# 4_waffling60-ALPS_periferals.net
KiCad netlist of a schematic drawn in Altium Designer
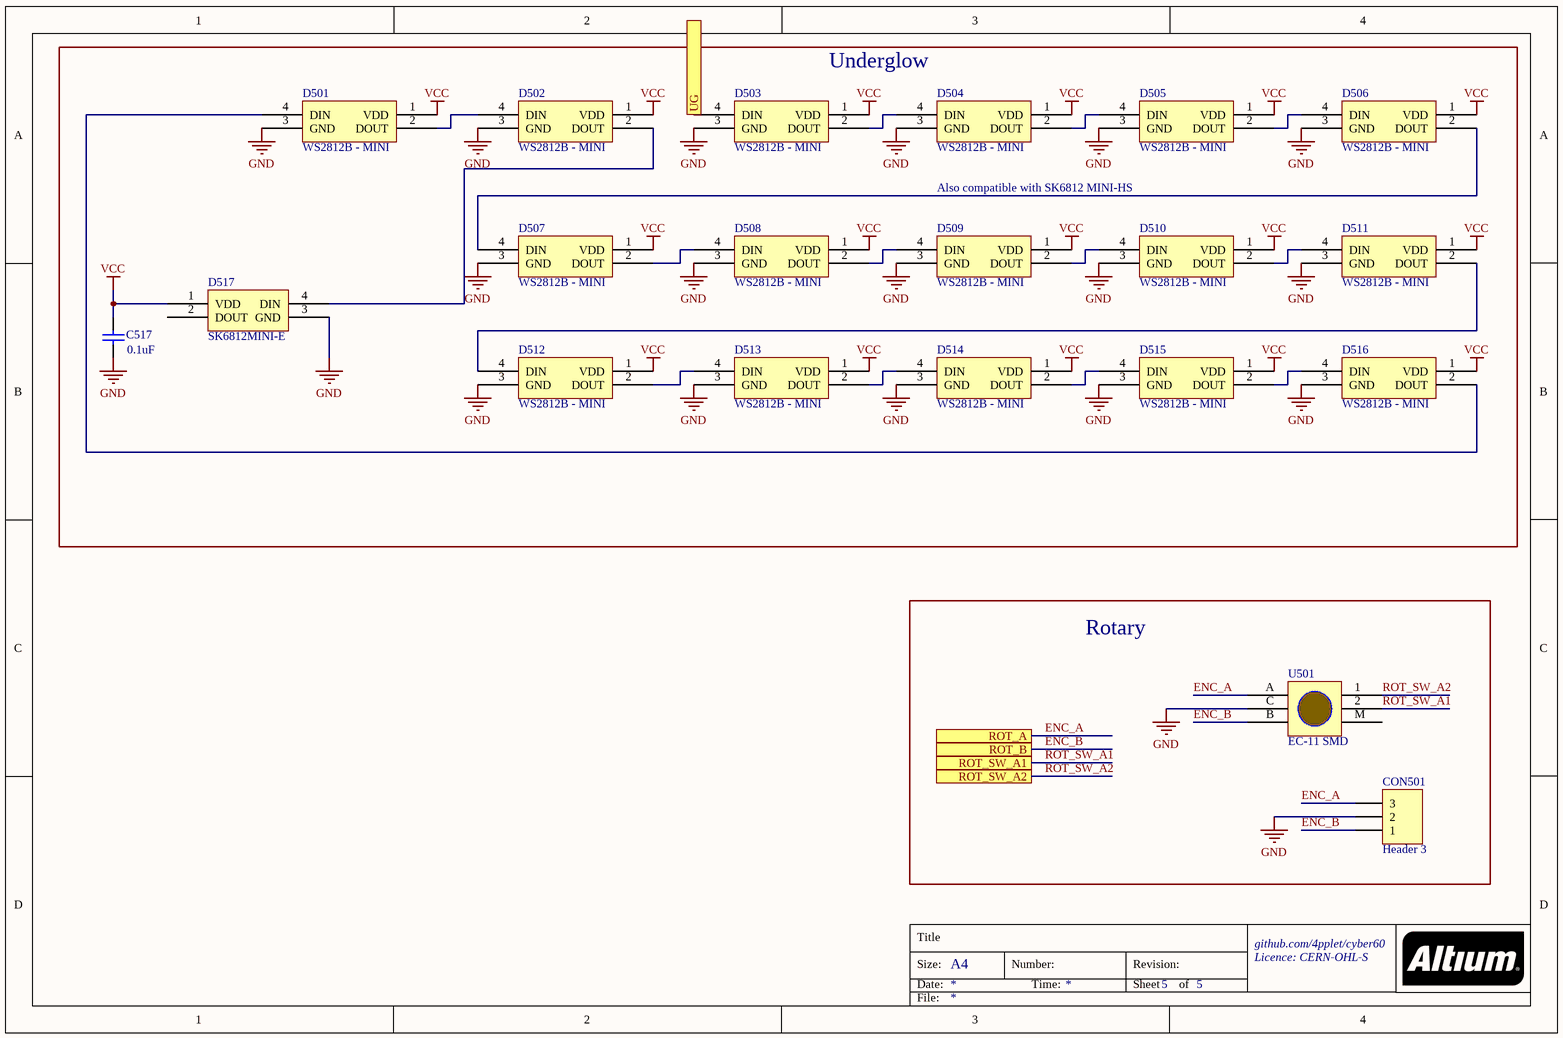
[diagram p0: 4_waffling60-ALPS_periferals.SchDoc]

(export (version "E")
  (design (tool "Eeschema 10.0.6"))
  (components
    (comp (ref "C517")
      (value "0.1uF")
      (footprint "C0603[1608]")
      (description "Capacitor")
      (fields (field (name "LCSC PART #") "C14663") (field (name "MRF.PART") "CC0603KRX7R9BB104"))
      (libsource (lib "Miscellaneous Devices") (part "Cap"))
    )
    (comp (ref "CON501")
      (value "Header 3")
      (footprint "HDR1X3")
      (description "Header, 3-Pin")
      (libsource (lib "Miscellaneous Connectors") (part "Header 3"))
    )
    (comp (ref "D501")
      (value "WS2812B - MINI")
      (footprint "WS2812B - 2020")
      (fields (field (name "LCSC PART #") "C965555") (field (name "MRF.PART") "WS2812B-2020"))
      (libsource (lib "Keebs") (part "WS2812B"))
    )
    (comp (ref "D502")
      (value "WS2812B - MINI")
      (footprint "WS2812B - 2020")
      (fields (field (name "LCSC PART #") "C965555") (field (name "MRF.PART") "WS2812B-2020"))
      (libsource (lib "Keebs") (part "WS2812B"))
    )
    (comp (ref "D503")
      (value "WS2812B - MINI")
      (footprint "WS2812B - 2020")
      (fields (field (name "LCSC PART #") "C965555") (field (name "MRF.PART") "WS2812B-2020"))
      (libsource (lib "Keebs") (part "WS2812B"))
    )
    (comp (ref "D504")
      (value "WS2812B - MINI")
      (footprint "WS2812B - 2020")
      (fields (field (name "LCSC PART #") "C965555") (field (name "MRF.PART") "WS2812B-2020"))
      (libsource (lib "Keebs") (part "WS2812B"))
    )
    (comp (ref "D505")
      (value "WS2812B - MINI")
      (footprint "WS2812B - 2020")
      (fields (field (name "LCSC PART #") "C965555") (field (name "MRF.PART") "WS2812B-2020"))
      (libsource (lib "Keebs") (part "WS2812B"))
    )
    (comp (ref "D506")
      (value "WS2812B - MINI")
      (footprint "WS2812B - 2020")
      (fields (field (name "LCSC PART #") "C965555") (field (name "MRF.PART") "WS2812B-2020"))
      (libsource (lib "Keebs") (part "WS2812B"))
    )
    (comp (ref "D507")
      (value "WS2812B - MINI")
      (footprint "WS2812B - 2020")
      (fields (field (name "LCSC PART #") "C965555") (field (name "MRF.PART") "WS2812B-2020"))
      (libsource (lib "Keebs") (part "WS2812B"))
    )
    (comp (ref "D508")
      (value "WS2812B - MINI")
      (footprint "WS2812B - 2020")
      (fields (field (name "LCSC PART #") "C965555") (field (name "MRF.PART") "WS2812B-2020"))
      (libsource (lib "Keebs") (part "WS2812B"))
    )
    (comp (ref "D509")
      (value "WS2812B - MINI")
      (footprint "WS2812B - 2020")
      (fields (field (name "LCSC PART #") "C965555") (field (name "MRF.PART") "WS2812B-2020"))
      (libsource (lib "Keebs") (part "WS2812B"))
    )
    (comp (ref "D510")
      (value "WS2812B - MINI")
      (footprint "WS2812B - 2020")
      (fields (field (name "LCSC PART #") "C965555") (field (name "MRF.PART") "WS2812B-2020"))
      (libsource (lib "Keebs") (part "WS2812B"))
    )
    (comp (ref "D511")
      (value "WS2812B - MINI")
      (footprint "WS2812B - 2020")
      (fields (field (name "LCSC PART #") "C965555") (field (name "MRF.PART") "WS2812B-2020"))
      (libsource (lib "Keebs") (part "WS2812B"))
    )
    (comp (ref "D512")
      (value "WS2812B - MINI")
      (footprint "WS2812B - 2020")
      (fields (field (name "LCSC PART #") "C965555") (field (name "MRF.PART") "WS2812B-2020"))
      (libsource (lib "Keebs") (part "WS2812B"))
    )
    (comp (ref "D513")
      (value "WS2812B - MINI")
      (footprint "WS2812B - 2020")
      (fields (field (name "LCSC PART #") "C965555") (field (name "MRF.PART") "WS2812B-2020"))
      (libsource (lib "Keebs") (part "WS2812B"))
    )
    (comp (ref "D514")
      (value "WS2812B - MINI")
      (footprint "WS2812B - 2020")
      (fields (field (name "LCSC PART #") "C965555") (field (name "MRF.PART") "WS2812B-2020"))
      (libsource (lib "Keebs") (part "WS2812B"))
    )
    (comp (ref "D515")
      (value "WS2812B - MINI")
      (footprint "WS2812B - 2020")
      (fields (field (name "LCSC PART #") "C965555") (field (name "MRF.PART") "WS2812B-2020"))
      (libsource (lib "Keebs") (part "WS2812B"))
    )
    (comp (ref "D516")
      (value "WS2812B - MINI")
      (footprint "WS2812B - 2020")
      (fields (field (name "LCSC PART #") "C965555") (field (name "MRF.PART") "WS2812B-2020"))
      (libsource (lib "Keebs") (part "WS2812B"))
    )
    (comp (ref "D517")
      (value "SK6812MINI-E")
      (footprint "SK6812MINI-E - shaped")
      (fields (field (name "LCSC PART #") "C524051") (field (name "MRF.PART") "DY-S352818/RGBC/6812-2T"))
      (libsource (lib "Keebs") (part "SK6812MINI-E"))
    )
    (comp (ref "U501") (value "EC-11 SMD") (footprint "EC11-SMD") (libsource (lib "Keebs") (part "EC-11")))
  )
  (nets
    (net (code "1") (name "/ENC_A") (class "Default")
      (node (ref "CON501") (pin "3") (pinfunction "3_3") (pintype "passive"))
      (node (ref "U501") (pin "A") (pinfunction "B_A") (pintype "passive"))
    )
    (net (code "2") (name "/ENC_B") (class "Default")
      (node (ref "CON501") (pin "1") (pinfunction "1_1") (pintype "passive"))
      (node (ref "U501") (pin "B") (pinfunction "B_B") (pintype "passive"))
    )
    (net (code "3") (name "/ROT_SW_A1") (class "Default")
      (node (ref "U501") (pin "2") (pinfunction "2_2") (pintype "passive"))
    )
    (net (code "4") (name "/ROT_SW_A2") (class "Default")
      (node (ref "U501") (pin "1") (pinfunction "1_1") (pintype "passive"))
    )
    (net (code "5") (name "/UG") (class "Default")
      (node (ref "D503") (pin "4") (pinfunction "DIN_4") (pintype "passive"))
    )
    (net (code "6") (name "GND") (class "Default")
      (node (ref "C517") (pin "1") (pinfunction "1_1") (pintype "passive"))
      (node (ref "CON501") (pin "2") (pinfunction "2_2") (pintype "passive"))
      (node (ref "D501") (pin "3") (pinfunction "GND_3") (pintype "passive"))
      (node (ref "D502") (pin "3") (pinfunction "GND_3") (pintype "passive"))
      (node (ref "D503") (pin "3") (pinfunction "GND_3") (pintype "passive"))
      (node (ref "D504") (pin "3") (pinfunction "GND_3") (pintype "passive"))
      (node (ref "D505") (pin "3") (pinfunction "GND_3") (pintype "passive"))
      (node (ref "D506") (pin "3") (pinfunction "GND_3") (pintype "passive"))
      (node (ref "D507") (pin "3") (pinfunction "GND_3") (pintype "passive"))
      (node (ref "D508") (pin "3") (pinfunction "GND_3") (pintype "passive"))
      (node (ref "D509") (pin "3") (pinfunction "GND_3") (pintype "passive"))
      (node (ref "D510") (pin "3") (pinfunction "GND_3") (pintype "passive"))
      (node (ref "D511") (pin "3") (pinfunction "GND_3") (pintype "passive"))
      (node (ref "D512") (pin "3") (pinfunction "GND_3") (pintype "passive"))
      (node (ref "D513") (pin "3") (pinfunction "GND_3") (pintype "passive"))
      (node (ref "D514") (pin "3") (pinfunction "GND_3") (pintype "passive"))
      (node (ref "D515") (pin "3") (pinfunction "GND_3") (pintype "passive"))
      (node (ref "D516") (pin "3") (pinfunction "GND_3") (pintype "passive"))
      (node (ref "D517") (pin "3") (pinfunction "GND_3") (pintype "passive"))
      (node (ref "U501") (pin "C") (pinfunction "C_C") (pintype "passive"))
    )
    (net (code "7") (name "Net-(D501-DIN)") (class "Default")
      (node (ref "D501") (pin "4") (pinfunction "DIN_4") (pintype "passive"))
      (node (ref "D516") (pin "2") (pinfunction "DOUT_2") (pintype "passive"))
    )
    (net (code "8") (name "Net-(D501-DOUT)") (class "Default")
      (node (ref "D501") (pin "2") (pinfunction "DOUT_2") (pintype "passive"))
      (node (ref "D502") (pin "4") (pinfunction "DIN_4") (pintype "passive"))
    )
    (net (code "9") (name "Net-(D502-DOUT)") (class "Default")
      (node (ref "D502") (pin "2") (pinfunction "DOUT_2") (pintype "passive"))
      (node (ref "D517") (pin "4") (pinfunction "DIN_4") (pintype "passive"))
    )
    (net (code "10") (name "Net-(D503-DOUT)") (class "Default")
      (node (ref "D503") (pin "2") (pinfunction "DOUT_2") (pintype "passive"))
      (node (ref "D504") (pin "4") (pinfunction "DIN_4") (pintype "passive"))
    )
    (net (code "11") (name "Net-(D504-DOUT)") (class "Default")
      (node (ref "D504") (pin "2") (pinfunction "DOUT_2") (pintype "passive"))
      (node (ref "D505") (pin "4") (pinfunction "DIN_4") (pintype "passive"))
    )
    (net (code "12") (name "Net-(D505-DOUT)") (class "Default")
      (node (ref "D505") (pin "2") (pinfunction "DOUT_2") (pintype "passive"))
      (node (ref "D506") (pin "4") (pinfunction "DIN_4") (pintype "passive"))
    )
    (net (code "13") (name "Net-(D506-DOUT)") (class "Default")
      (node (ref "D506") (pin "2") (pinfunction "DOUT_2") (pintype "passive"))
      (node (ref "D507") (pin "4") (pinfunction "DIN_4") (pintype "passive"))
    )
    (net (code "14") (name "Net-(D507-DOUT)") (class "Default")
      (node (ref "D507") (pin "2") (pinfunction "DOUT_2") (pintype "passive"))
      (node (ref "D508") (pin "4") (pinfunction "DIN_4") (pintype "passive"))
    )
    (net (code "15") (name "Net-(D508-DOUT)") (class "Default")
      (node (ref "D508") (pin "2") (pinfunction "DOUT_2") (pintype "passive"))
      (node (ref "D509") (pin "4") (pinfunction "DIN_4") (pintype "passive"))
    )
    (net (code "16") (name "Net-(D509-DOUT)") (class "Default")
      (node (ref "D509") (pin "2") (pinfunction "DOUT_2") (pintype "passive"))
      (node (ref "D510") (pin "4") (pinfunction "DIN_4") (pintype "passive"))
    )
    (net (code "17") (name "Net-(D510-DOUT)") (class "Default")
      (node (ref "D510") (pin "2") (pinfunction "DOUT_2") (pintype "passive"))
      (node (ref "D511") (pin "4") (pinfunction "DIN_4") (pintype "passive"))
    )
    (net (code "18") (name "Net-(D511-DOUT)") (class "Default")
      (node (ref "D511") (pin "2") (pinfunction "DOUT_2") (pintype "passive"))
      (node (ref "D512") (pin "4") (pinfunction "DIN_4") (pintype "passive"))
    )
    (net (code "19") (name "Net-(D512-DOUT)") (class "Default")
      (node (ref "D512") (pin "2") (pinfunction "DOUT_2") (pintype "passive"))
      (node (ref "D513") (pin "4") (pinfunction "DIN_4") (pintype "passive"))
    )
    (net (code "20") (name "Net-(D513-DOUT)") (class "Default")
      (node (ref "D513") (pin "2") (pinfunction "DOUT_2") (pintype "passive"))
      (node (ref "D514") (pin "4") (pinfunction "DIN_4") (pintype "passive"))
    )
    (net (code "21") (name "Net-(D514-DOUT)") (class "Default")
      (node (ref "D514") (pin "2") (pinfunction "DOUT_2") (pintype "passive"))
      (node (ref "D515") (pin "4") (pinfunction "DIN_4") (pintype "passive"))
    )
    (net (code "22") (name "Net-(D515-DOUT)") (class "Default")
      (node (ref "D515") (pin "2") (pinfunction "DOUT_2") (pintype "passive"))
      (node (ref "D516") (pin "4") (pinfunction "DIN_4") (pintype "passive"))
    )
    (net (code "23") (name "VCC") (class "Default")
      (node (ref "C517") (pin "2") (pinfunction "2_2") (pintype "passive"))
      (node (ref "D501") (pin "1") (pinfunction "VDD_1") (pintype "passive"))
      (node (ref "D502") (pin "1") (pinfunction "VDD_1") (pintype "passive"))
      (node (ref "D503") (pin "1") (pinfunction "VDD_1") (pintype "passive"))
      (node (ref "D504") (pin "1") (pinfunction "VDD_1") (pintype "passive"))
      (node (ref "D505") (pin "1") (pinfunction "VDD_1") (pintype "passive"))
      (node (ref "D506") (pin "1") (pinfunction "VDD_1") (pintype "passive"))
      (node (ref "D507") (pin "1") (pinfunction "VDD_1") (pintype "passive"))
      (node (ref "D508") (pin "1") (pinfunction "VDD_1") (pintype "passive"))
      (node (ref "D509") (pin "1") (pinfunction "VDD_1") (pintype "passive"))
      (node (ref "D510") (pin "1") (pinfunction "VDD_1") (pintype "passive"))
      (node (ref "D511") (pin "1") (pinfunction "VDD_1") (pintype "passive"))
      (node (ref "D512") (pin "1") (pinfunction "VDD_1") (pintype "passive"))
      (node (ref "D513") (pin "1") (pinfunction "VDD_1") (pintype "passive"))
      (node (ref "D514") (pin "1") (pinfunction "VDD_1") (pintype "passive"))
      (node (ref "D515") (pin "1") (pinfunction "VDD_1") (pintype "passive"))
      (node (ref "D516") (pin "1") (pinfunction "VDD_1") (pintype "passive"))
      (node (ref "D517") (pin "1") (pinfunction "VDD_1") (pintype "passive"))
    )
    (net (code "24") (name "unconnected-(D517-DOUT-Pad2)") (class "Default")
      (node (ref "D517") (pin "2") (pinfunction "DOUT_2") (pintype "passive"))
    )
    (net (code "25") (name "unconnected-(U501-PadM)") (class "Default")
      (node (ref "U501") (pin "M") (pinfunction "M_M") (pintype "passive"))
    )
  )
)
